# BotMotShielArdu.net
KiCad netlist of a schematic drawn in EAGLE
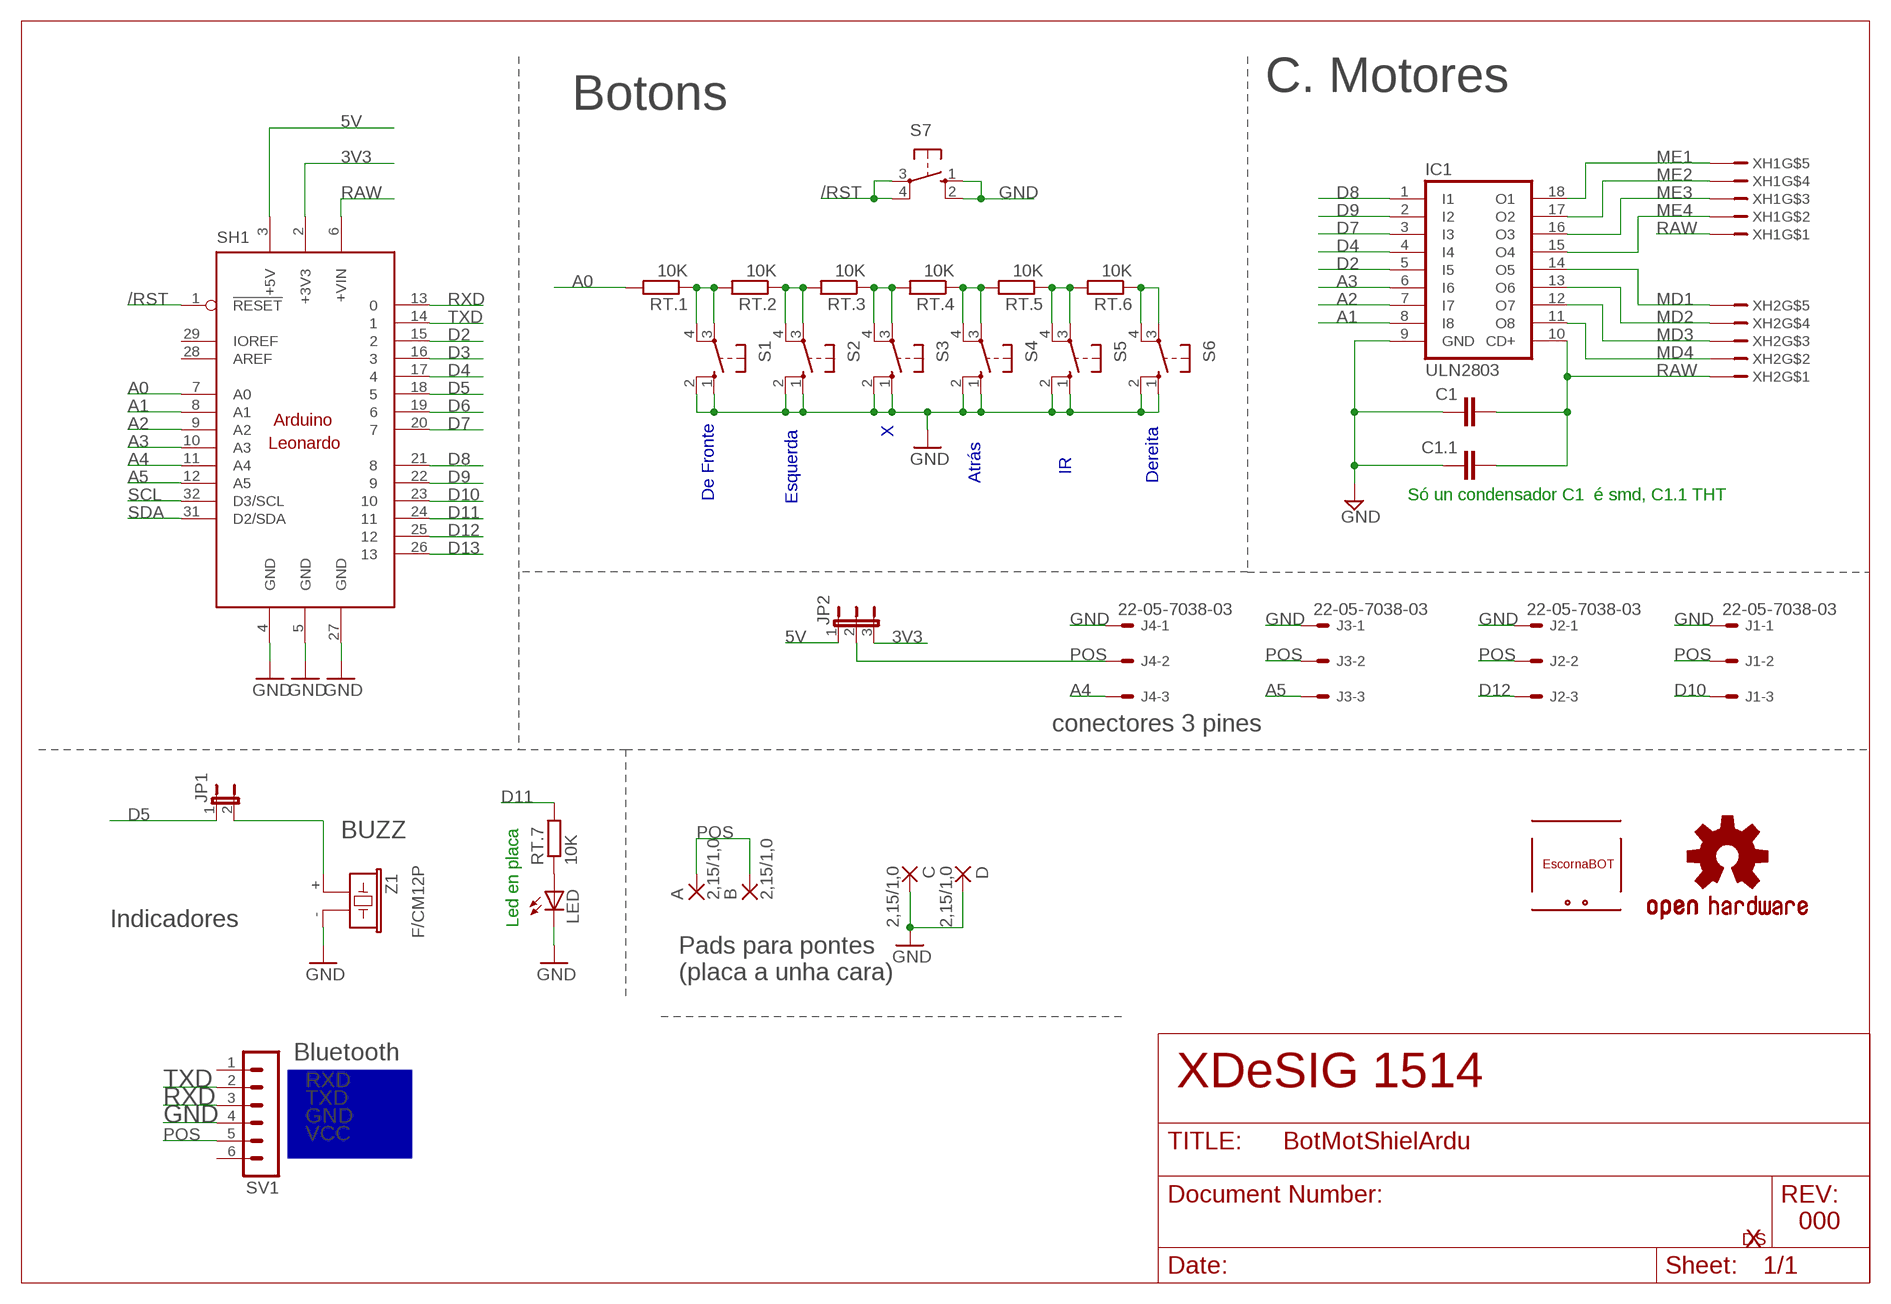
[diagram p0: schematic, sheet 1]

(export (version "E")
  (design (tool "Eeschema 10.0.6"))
  (components
    (comp (ref "A")
      (value "2,15/1,0")
      (footprint "eagle-import:2,15_1,0")
      (libsource (lib "eagle-import") (part "WIREPAD2,15/1,0"))
    )
    (comp (ref "B")
      (value "2,15/1,0")
      (footprint "eagle-import:2,15_1,0")
      (libsource (lib "eagle-import") (part "WIREPAD2,15/1,0"))
    )
    (comp (ref "C")
      (value "2,15/1,0")
      (footprint "eagle-import:2,15_1,0")
      (libsource (lib "eagle-import") (part "WIREPAD2,15/1,0"))
    )
    (comp (ref "C1")
      (value "C-EUC1206")
      (footprint "eagle-import:C1206")
      (libsource (lib "eagle-import") (part "C-EUC1206"))
    )
    (comp (ref "C1.1")
      (value "C-EU025-024X044")
      (footprint "eagle-import:C025-024X044")
      (libsource (lib "eagle-import") (part "C-EU025-024X044"))
    )
    (comp (ref "D")
      (value "2,15/1,0")
      (footprint "eagle-import:2,15_1,0")
      (libsource (lib "eagle-import") (part "WIREPAD2,15/1,0"))
    )
    (comp (ref "IC1")
      (value "ULN2803")
      (footprint "eagle-import:DIL18")
      (libsource (lib "eagle-import") (part "ULN2803A"))
    )
    (comp (ref "J1")
      (value "22-05-7038-03")
      (footprint "eagle-import:7395-03")
      (libsource (lib "eagle-import") (part "22-?-0305-7038"))
    )
    (comp (ref "J2")
      (value "22-05-7038-03")
      (footprint "eagle-import:7395-03")
      (libsource (lib "eagle-import") (part "22-?-0305-7038"))
    )
    (comp (ref "J3")
      (value "22-05-7038-03")
      (footprint "eagle-import:7395-03")
      (libsource (lib "eagle-import") (part "22-?-0305-7038"))
    )
    (comp (ref "J4")
      (value "22-05-7038-03")
      (footprint "eagle-import:7395-03")
      (libsource (lib "eagle-import") (part "22-?-0305-7038"))
    )
    (comp (ref "JP1")
      (value "JP1E")
      (footprint "eagle-import:JP1")
      (libsource (lib "eagle-import") (part "JP1E"))
    )
    (comp (ref "JP2")
      (value "JP2E")
      (footprint "eagle-import:JP2")
      (libsource (lib "eagle-import") (part "JP2E"))
    )
    (comp (ref "LED")
      (value "LED5MM")
      (footprint "eagle-import:LED5MM")
      (libsource (lib "eagle-import") (part "LED5MM"))
    )
    (comp (ref "LOGO4")
      (value "OSHW-LOGOS")
      (footprint "eagle-import:OSHW-LOGO-S")
      (libsource (lib "eagle-import") (part "OSHW-LOGOS"))
    )
    (comp (ref "RT.1")
      (value "10K")
      (footprint "eagle-import:0204_7")
      (libsource (lib "eagle-import") (part "R-EU_0204/7"))
    )
    (comp (ref "RT.2")
      (value "10K")
      (footprint "eagle-import:0204_7")
      (libsource (lib "eagle-import") (part "R-EU_0204/7"))
    )
    (comp (ref "RT.3")
      (value "10K")
      (footprint "eagle-import:0204_7")
      (libsource (lib "eagle-import") (part "R-EU_0204/7"))
    )
    (comp (ref "RT.4")
      (value "10K")
      (footprint "eagle-import:0204_7")
      (libsource (lib "eagle-import") (part "R-EU_0204/7"))
    )
    (comp (ref "RT.5")
      (value "10K")
      (footprint "eagle-import:0204_7")
      (libsource (lib "eagle-import") (part "R-EU_0204/7"))
    )
    (comp (ref "RT.6")
      (value "10K")
      (footprint "eagle-import:0204_7")
      (libsource (lib "eagle-import") (part "R-EU_0204/7"))
    )
    (comp (ref "RT.7")
      (value "10K")
      (footprint "eagle-import:0204_7")
      (libsource (lib "eagle-import") (part "R-EU_0204/7"))
    )
    (comp (ref "S1")
      (value "B3F-40XX")
      (footprint "eagle-import:B3F40XX_NH")
      (libsource (lib "eagle-import") (part "40-XX"))
    )
    (comp (ref "S2")
      (value "B3F-40XX")
      (footprint "eagle-import:B3F40XX_NH")
      (libsource (lib "eagle-import") (part "40-XX"))
    )
    (comp (ref "S3")
      (value "B3F-40XX")
      (footprint "eagle-import:B3F40XX_NH")
      (libsource (lib "eagle-import") (part "40-XX"))
    )
    (comp (ref "S4")
      (value "B3F-40XX")
      (footprint "eagle-import:B3F40XX_NH")
      (libsource (lib "eagle-import") (part "40-XX"))
    )
    (comp (ref "S5")
      (value "B3F-40XX")
      (footprint "eagle-import:B3F40XX_NH")
      (libsource (lib "eagle-import") (part "40-XX"))
    )
    (comp (ref "S6")
      (value "B3F-40XX")
      (footprint "eagle-import:B3F40XX_NH")
      (libsource (lib "eagle-import") (part "40-XX"))
    )
    (comp (ref "S7")
      (value "10-XX")
      (footprint "eagle-import:B3F-10XX")
      (fields (field (name "MPN") "B3F-1000"))
      (libsource (lib "eagle-import") (part "10-XX"))
    )
    (comp (ref "SH1")
      (value "ARDUINO_LEONARDO")
      (footprint "eagle-import:LEONARDO")
      (libsource (lib "eagle-import") (part "ARDUINO_LEONARDO"))
    )
    (comp (ref "SV1")
      (value "MA06-1")
      (footprint "eagle-import:MA06-1")
      (libsource (lib "eagle-import") (part "MA06-1"))
    )
    (comp (ref "U$1")
      (value "ESCORNABOT")
      (footprint "eagle-import:ESCORNA_PEQUE")
      (libsource (lib "eagle-import") (part "ESCORNABOT"))
    )
    (comp (ref "U$3")
      (value "XDESIG1")
      (footprint "eagle-import:XDESIG_CU")
      (libsource (lib "eagle-import") (part "XDESIG1"))
    )
    (comp (ref "XH1")
      (value "B5B-XH-A")
      (footprint "eagle-import:B5B-XH-A")
      (libsource (lib "eagle-import") (part "B5B-XH-A"))
    )
    (comp (ref "XH2")
      (value "B5B-XH-A")
      (footprint "eagle-import:B5B-XH-A")
      (libsource (lib "eagle-import") (part "B5B-XH-A"))
    )
    (comp (ref "Z1")
      (value "F/CM12P")
      (footprint "eagle-import:F_CM12P")
      (libsource (lib "eagle-import") (part "F/CM12P"))
    )
  )
  (nets
    (net (code "1") (name "/3V3") (class "Default")
      (node (ref "JP2") (pin "3") (pinfunction "3_3") (pintype "passive"))
      (node (ref "SH1") (pin "2") (pinfunction "+3V3_2") (pintype "power_in"))
    )
    (net (code "2") (name "/5V") (class "Default")
      (node (ref "JP2") (pin "1") (pinfunction "1_1") (pintype "passive"))
      (node (ref "SH1") (pin "3") (pinfunction "+5V_3") (pintype "power_in"))
    )
    (net (code "3") (name "/A0") (class "Default")
      (node (ref "RT.1") (pin "2") (pinfunction "2_2") (pintype "passive"))
      (node (ref "SH1") (pin "7") (pinfunction "A0_7") (pintype "bidirectional"))
    )
    (net (code "4") (name "/A1") (class "Default")
      (node (ref "IC1") (pin "8") (pinfunction "I8_8") (pintype "input"))
      (node (ref "SH1") (pin "8") (pinfunction "A1_8") (pintype "bidirectional"))
    )
    (net (code "5") (name "/A2") (class "Default")
      (node (ref "IC1") (pin "7") (pinfunction "I7_7") (pintype "input"))
      (node (ref "SH1") (pin "9") (pinfunction "A2_9") (pintype "bidirectional"))
    )
    (net (code "6") (name "/A3") (class "Default")
      (node (ref "IC1") (pin "6") (pinfunction "I6_6") (pintype "input"))
      (node (ref "SH1") (pin "10") (pinfunction "A3_10") (pintype "bidirectional"))
    )
    (net (code "7") (name "/A4") (class "Default")
      (node (ref "J4") (pin "3") (pinfunction "S_3") (pintype "passive"))
      (node (ref "SH1") (pin "11") (pinfunction "A4_11") (pintype "bidirectional"))
    )
    (net (code "8") (name "/A5") (class "Default")
      (node (ref "J3") (pin "3") (pinfunction "S_3") (pintype "passive"))
      (node (ref "SH1") (pin "12") (pinfunction "A5_12") (pintype "bidirectional"))
    )
    (net (code "9") (name "/D2") (class "Default")
      (node (ref "IC1") (pin "5") (pinfunction "I5_5") (pintype "input"))
      (node (ref "SH1") (pin "15") (pinfunction "2_15") (pintype "bidirectional"))
    )
    (net (code "10") (name "/D3") (class "Default")
      (node (ref "SH1") (pin "16") (pinfunction "3_16") (pintype "bidirectional"))
    )
    (net (code "11") (name "/D4") (class "Default")
      (node (ref "IC1") (pin "4") (pinfunction "I4_4") (pintype "input"))
      (node (ref "SH1") (pin "17") (pinfunction "4_17") (pintype "bidirectional"))
    )
    (net (code "12") (name "/D5") (class "Default")
      (node (ref "JP1") (pin "1") (pinfunction "1_1") (pintype "passive"))
      (node (ref "SH1") (pin "18") (pinfunction "5_18") (pintype "bidirectional"))
    )
    (net (code "13") (name "/D6") (class "Default")
      (node (ref "SH1") (pin "19") (pinfunction "6_19") (pintype "bidirectional"))
    )
    (net (code "14") (name "/D7") (class "Default")
      (node (ref "IC1") (pin "3") (pinfunction "I3_3") (pintype "input"))
      (node (ref "SH1") (pin "20") (pinfunction "7_20") (pintype "bidirectional"))
    )
    (net (code "15") (name "/D8") (class "Default")
      (node (ref "IC1") (pin "1") (pinfunction "I1_1") (pintype "input"))
      (node (ref "SH1") (pin "21") (pinfunction "8_21") (pintype "bidirectional"))
    )
    (net (code "16") (name "/D9") (class "Default")
      (node (ref "IC1") (pin "2") (pinfunction "I2_2") (pintype "input"))
      (node (ref "SH1") (pin "22") (pinfunction "9_22") (pintype "bidirectional"))
    )
    (net (code "17") (name "/D10") (class "Default")
      (node (ref "J1") (pin "3") (pinfunction "S_3") (pintype "passive"))
      (node (ref "SH1") (pin "23") (pinfunction "10_23") (pintype "bidirectional"))
    )
    (net (code "18") (name "/D11") (class "Default")
      (node (ref "RT.7") (pin "2") (pinfunction "2_2") (pintype "passive"))
      (node (ref "SH1") (pin "24") (pinfunction "11_24") (pintype "bidirectional"))
    )
    (net (code "19") (name "/D12") (class "Default")
      (node (ref "J2") (pin "3") (pinfunction "S_3") (pintype "passive"))
      (node (ref "SH1") (pin "25") (pinfunction "12_25") (pintype "bidirectional"))
    )
    (net (code "20") (name "/D13") (class "Default")
      (node (ref "SH1") (pin "26") (pinfunction "13_26") (pintype "bidirectional"))
    )
    (net (code "21") (name "/MD1") (class "Default")
      (node (ref "IC1") (pin "14") (pinfunction "O5_14") (pintype "open_collector"))
      (node (ref "XH2") (pin "P$5") (pinfunction "1_P$5") (pintype "passive"))
    )
    (net (code "22") (name "/MD2") (class "Default")
      (node (ref "IC1") (pin "13") (pinfunction "O6_13") (pintype "open_collector"))
      (node (ref "XH2") (pin "P$4") (pinfunction "1_P$4") (pintype "passive"))
    )
    (net (code "23") (name "/MD3") (class "Default")
      (node (ref "IC1") (pin "12") (pinfunction "O7_12") (pintype "open_collector"))
      (node (ref "XH2") (pin "P$3") (pinfunction "1_P$3") (pintype "passive"))
    )
    (net (code "24") (name "/MD4") (class "Default")
      (node (ref "IC1") (pin "11") (pinfunction "O8_11") (pintype "open_collector"))
      (node (ref "XH2") (pin "P$2") (pinfunction "1_P$2") (pintype "passive"))
    )
    (net (code "25") (name "/ME1") (class "Default")
      (node (ref "IC1") (pin "18") (pinfunction "O1_18") (pintype "open_collector"))
      (node (ref "XH1") (pin "P$5") (pinfunction "1_P$5") (pintype "passive"))
    )
    (net (code "26") (name "/ME2") (class "Default")
      (node (ref "IC1") (pin "17") (pinfunction "O2_17") (pintype "open_collector"))
      (node (ref "XH1") (pin "P$4") (pinfunction "1_P$4") (pintype "passive"))
    )
    (net (code "27") (name "/ME3") (class "Default")
      (node (ref "IC1") (pin "16") (pinfunction "O3_16") (pintype "open_collector"))
      (node (ref "XH1") (pin "P$3") (pinfunction "1_P$3") (pintype "passive"))
    )
    (net (code "28") (name "/ME4") (class "Default")
      (node (ref "IC1") (pin "15") (pinfunction "O4_15") (pintype "open_collector"))
      (node (ref "XH1") (pin "P$2") (pinfunction "1_P$2") (pintype "passive"))
    )
    (net (code "29") (name "/POS") (class "Default")
      (node (ref "A") (pin "1") (pinfunction "P_1") (pintype "passive"))
      (node (ref "B") (pin "1") (pinfunction "P_1") (pintype "passive"))
      (node (ref "J1") (pin "2") (pinfunction "S_2") (pintype "passive"))
      (node (ref "J2") (pin "2") (pinfunction "S_2") (pintype "passive"))
      (node (ref "J3") (pin "2") (pinfunction "S_2") (pintype "passive"))
      (node (ref "J4") (pin "2") (pinfunction "S_2") (pintype "passive"))
      (node (ref "JP2") (pin "2") (pinfunction "2_2") (pintype "passive"))
      (node (ref "SV1") (pin "5") (pinfunction "5_5") (pintype "passive"))
    )
    (net (code "30") (name "/RAW") (class "Default")
      (node (ref "C1") (pin "2") (pinfunction "2_2") (pintype "passive"))
      (node (ref "C1.1") (pin "2") (pinfunction "2_2") (pintype "passive"))
      (node (ref "IC1") (pin "10") (pinfunction "CD+_10") (pintype "passive"))
      (node (ref "SH1") (pin "6") (pinfunction "+VIN_6") (pintype "bidirectional"))
      (node (ref "XH1") (pin "P$1") (pinfunction "1_P$1") (pintype "passive"))
      (node (ref "XH2") (pin "P$1") (pinfunction "1_P$1") (pintype "passive"))
    )
    (net (code "31") (name "/RXD") (class "Default")
      (node (ref "SH1") (pin "13") (pinfunction "0_13") (pintype "bidirectional"))
      (node (ref "SV1") (pin "3") (pinfunction "3_3") (pintype "passive"))
    )
    (net (code "32") (name "/SCL") (class "Default")
      (node (ref "SH1") (pin "32") (pinfunction "D3/SCL_32") (pintype "bidirectional"))
    )
    (net (code "33") (name "/SDA") (class "Default")
      (node (ref "SH1") (pin "31") (pinfunction "D2/SDA_31") (pintype "bidirectional"))
    )
    (net (code "34") (name "/TXD") (class "Default")
      (node (ref "SH1") (pin "14") (pinfunction "1_14") (pintype "bidirectional"))
      (node (ref "SV1") (pin "2") (pinfunction "2_2") (pintype "passive"))
    )
    (net (code "35") (name "/{slash}RST") (class "Default")
      (node (ref "S7") (pin "3") (pinfunction "P_3") (pintype "passive"))
      (node (ref "S7") (pin "4") (pinfunction "P1_4") (pintype "passive"))
      (node (ref "SH1") (pin "1") (pinfunction "~{RESET}_1") (pintype "bidirectional"))
    )
    (net (code "36") (name "GND") (class "Default")
      (node (ref "C") (pin "1") (pinfunction "P_1") (pintype "passive"))
      (node (ref "C1") (pin "1") (pinfunction "1_1") (pintype "passive"))
      (node (ref "C1.1") (pin "1") (pinfunction "1_1") (pintype "passive"))
      (node (ref "D") (pin "1") (pinfunction "P_1") (pintype "passive"))
      (node (ref "IC1") (pin "9") (pinfunction "GND_9") (pintype "power_in"))
      (node (ref "J1") (pin "1") (pinfunction "S_1") (pintype "passive"))
      (node (ref "J2") (pin "1") (pinfunction "S_1") (pintype "passive"))
      (node (ref "J3") (pin "1") (pinfunction "S_1") (pintype "passive"))
      (node (ref "J4") (pin "1") (pinfunction "S_1") (pintype "passive"))
      (node (ref "LED") (pin "K") (pinfunction "C_K") (pintype "passive"))
      (node (ref "S1") (pin "1") (pinfunction "S_1") (pintype "passive"))
      (node (ref "S1") (pin "2") (pinfunction "S1_2") (pintype "passive"))
      (node (ref "S2") (pin "1") (pinfunction "S_1") (pintype "passive"))
      (node (ref "S2") (pin "2") (pinfunction "S1_2") (pintype "passive"))
      (node (ref "S3") (pin "1") (pinfunction "S_1") (pintype "passive"))
      (node (ref "S3") (pin "2") (pinfunction "S1_2") (pintype "passive"))
      (node (ref "S4") (pin "1") (pinfunction "S_1") (pintype "passive"))
      (node (ref "S4") (pin "2") (pinfunction "S1_2") (pintype "passive"))
      (node (ref "S5") (pin "1") (pinfunction "S_1") (pintype "passive"))
      (node (ref "S5") (pin "2") (pinfunction "S1_2") (pintype "passive"))
      (node (ref "S6") (pin "1") (pinfunction "S_1") (pintype "passive"))
      (node (ref "S6") (pin "2") (pinfunction "S1_2") (pintype "passive"))
      (node (ref "S7") (pin "1") (pinfunction "S_1") (pintype "passive"))
      (node (ref "S7") (pin "2") (pinfunction "S1_2") (pintype "passive"))
      (node (ref "SH1") (pin "27") (pinfunction "GND_27") (pintype "power_in"))
      (node (ref "SH1") (pin "4") (pinfunction "GND_4") (pintype "power_in"))
      (node (ref "SH1") (pin "5") (pinfunction "GND_5") (pintype "power_in"))
      (node (ref "SV1") (pin "4") (pinfunction "4_4") (pintype "passive"))
      (node (ref "Z1") (pin "-") (pinfunction "2_-") (pintype "passive"))
    )
    (net (code "37") (name "Net-(LED-PadA)") (class "Default")
      (node (ref "LED") (pin "A") (pinfunction "A_A") (pintype "passive"))
      (node (ref "RT.7") (pin "1") (pinfunction "1_1") (pintype "passive"))
    )
    (net (code "38") (name "Net-(S1-P)") (class "Default")
      (node (ref "RT.1") (pin "1") (pinfunction "1_1") (pintype "passive"))
      (node (ref "RT.2") (pin "2") (pinfunction "2_2") (pintype "passive"))
      (node (ref "S1") (pin "3") (pinfunction "P_3") (pintype "passive"))
      (node (ref "S1") (pin "4") (pinfunction "P1_4") (pintype "passive"))
    )
    (net (code "39") (name "Net-(S2-P)") (class "Default")
      (node (ref "RT.2") (pin "1") (pinfunction "1_1") (pintype "passive"))
      (node (ref "RT.3") (pin "2") (pinfunction "2_2") (pintype "passive"))
      (node (ref "S2") (pin "3") (pinfunction "P_3") (pintype "passive"))
      (node (ref "S2") (pin "4") (pinfunction "P1_4") (pintype "passive"))
    )
    (net (code "40") (name "Net-(S3-P)") (class "Default")
      (node (ref "RT.3") (pin "1") (pinfunction "1_1") (pintype "passive"))
      (node (ref "RT.4") (pin "2") (pinfunction "2_2") (pintype "passive"))
      (node (ref "S3") (pin "3") (pinfunction "P_3") (pintype "passive"))
      (node (ref "S3") (pin "4") (pinfunction "P1_4") (pintype "passive"))
    )
    (net (code "41") (name "Net-(S4-P)") (class "Default")
      (node (ref "RT.4") (pin "1") (pinfunction "1_1") (pintype "passive"))
      (node (ref "RT.5") (pin "2") (pinfunction "2_2") (pintype "passive"))
      (node (ref "S4") (pin "3") (pinfunction "P_3") (pintype "passive"))
      (node (ref "S4") (pin "4") (pinfunction "P1_4") (pintype "passive"))
    )
    (net (code "42") (name "Net-(S5-P)") (class "Default")
      (node (ref "RT.5") (pin "1") (pinfunction "1_1") (pintype "passive"))
      (node (ref "RT.6") (pin "2") (pinfunction "2_2") (pintype "passive"))
      (node (ref "S5") (pin "3") (pinfunction "P_3") (pintype "passive"))
      (node (ref "S5") (pin "4") (pinfunction "P1_4") (pintype "passive"))
    )
    (net (code "43") (name "Net-(S6-P)") (class "Default")
      (node (ref "RT.6") (pin "1") (pinfunction "1_1") (pintype "passive"))
      (node (ref "S6") (pin "3") (pinfunction "P_3") (pintype "passive"))
      (node (ref "S6") (pin "4") (pinfunction "P1_4") (pintype "passive"))
    )
    (net (code "44") (name "Net-(Z1-1)") (class "Default")
      (node (ref "JP1") (pin "2") (pinfunction "2_2") (pintype "passive"))
      (node (ref "Z1") (pin "+") (pinfunction "1_+") (pintype "passive"))
    )
    (net (code "45") (name "unconnected-(SH1-AREF-Pad28)") (class "Default")
      (node (ref "SH1") (pin "28") (pinfunction "AREF_28") (pintype "bidirectional"))
    )
    (net (code "46") (name "unconnected-(SH1-IOREF-Pad29)") (class "Default")
      (node (ref "SH1") (pin "29") (pinfunction "IOREF_29") (pintype "bidirectional"))
    )
    (net (code "47") (name "unconnected-(SV1-Pad1)") (class "Default")
      (node (ref "SV1") (pin "1") (pinfunction "1_1") (pintype "passive"))
    )
    (net (code "48") (name "unconnected-(SV1-Pad6)") (class "Default")
      (node (ref "SV1") (pin "6") (pinfunction "6_6") (pintype "passive"))
    )
  )
)
